# Steering_Wheel_Steering_Stalk_Connector.net
KiCad netlist of a schematic drawn in Altium Designer
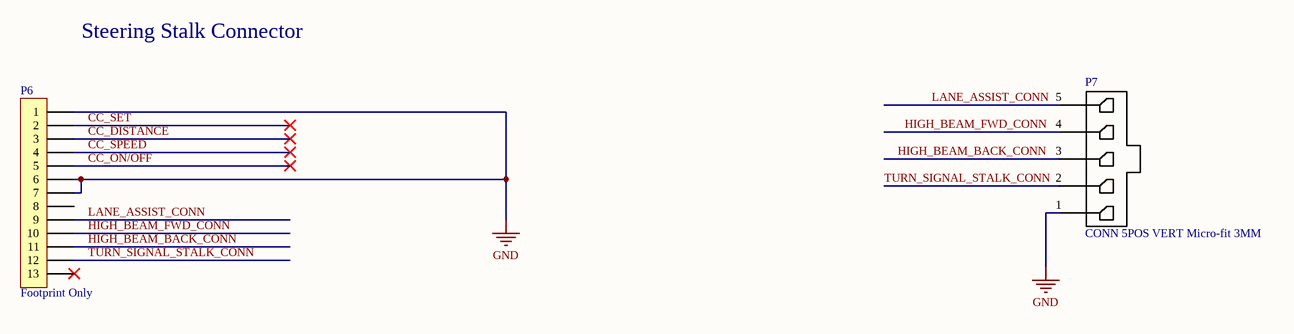
[diagram p0: Steering Wheel Steering Stalk Connector.SchDoc]

(export (version "E")
  (design (tool "Eeschema 10.0.6"))
  (components
    (comp (ref "P6")
      (value "Footprint Only")
      (footprint "CONN 13POS CARD EDGE")
      (libsource (lib "Schematic Diagrams") (part "CONN 13POS 0.1{dblquote} CARD EDGE"))
    )
    (comp (ref "P7")
      (value "CONN 5POS VERT Micro-fit 3MM")
      (footprint "CONN, 5POS MICRO-FIT 3mm")
      (description "Conn Power HDR 5 POS 3mm Solder ST Thru-Hole 5 Terminal 1 Port Micro-Fit 3.0™ Tray")
      (fields (field (name "MANUFACTURER PART NUMBER") "0436500516") (field (name "MANUFACTURER") "Molex"))
      (libsource (lib "University of Waterloo - Solar Car Team") (part "CONN 5POS VERT Micro-fit 3MM"))
    )
  )
  (nets
    (net (code "1") (name "/CC_DISTANCE") (class "Default")
      (node (ref "P6") (pin "3") (pinfunction "3_3") (pintype "passive+no_connect"))
    )
    (net (code "2") (name "/CC_ON{slash}~{OFF}") (class "Default")
      (node (ref "P6") (pin "5") (pinfunction "5_5") (pintype "passive+no_connect"))
    )
    (net (code "3") (name "/CC_SET") (class "Default")
      (node (ref "P6") (pin "2") (pinfunction "2_2") (pintype "passive+no_connect"))
    )
    (net (code "4") (name "/CC_SPEED") (class "Default")
      (node (ref "P6") (pin "4") (pinfunction "4_4") (pintype "passive+no_connect"))
    )
    (net (code "5") (name "/HIGH_BEAM_BACK_CONN") (class "Default")
      (node (ref "P6") (pin "11") (pinfunction "11_11") (pintype "passive"))
      (node (ref "P7") (pin "3") (pinfunction "3_3") (pintype "passive"))
    )
    (net (code "6") (name "/HIGH_BEAM_FWD_CONN") (class "Default")
      (node (ref "P6") (pin "10") (pinfunction "10_10") (pintype "passive"))
      (node (ref "P7") (pin "4") (pinfunction "4_4") (pintype "passive"))
    )
    (net (code "7") (name "/LANE_ASSIST_CONN") (class "Default")
      (node (ref "P6") (pin "9") (pinfunction "9_9") (pintype "passive"))
      (node (ref "P7") (pin "5") (pinfunction "5_5") (pintype "passive"))
    )
    (net (code "8") (name "/TURN_SIGNAL_STALK_CONN") (class "Default")
      (node (ref "P6") (pin "12") (pinfunction "12_12") (pintype "passive"))
      (node (ref "P7") (pin "2") (pinfunction "2_2") (pintype "passive"))
    )
    (net (code "9") (name "GND") (class "Default")
      (node (ref "P6") (pin "1") (pinfunction "1_1") (pintype "passive"))
      (node (ref "P6") (pin "6") (pinfunction "6_6") (pintype "passive"))
      (node (ref "P6") (pin "7") (pinfunction "7_7") (pintype "passive"))
      (node (ref "P7") (pin "1") (pinfunction "1_1") (pintype "passive"))
    )
    (net (code "10") (name "unconnected-(P6-Pad8)") (class "Default")
      (node (ref "P6") (pin "8") (pinfunction "8_8") (pintype "passive"))
    )
    (net (code "11") (name "unconnected-(P6-Pad13)") (class "Default")
      (node (ref "P6") (pin "13") (pinfunction "13_13") (pintype "passive+no_connect"))
    )
  )
)
